# PD.net
KiCad netlist of a schematic drawn in Altium Designer
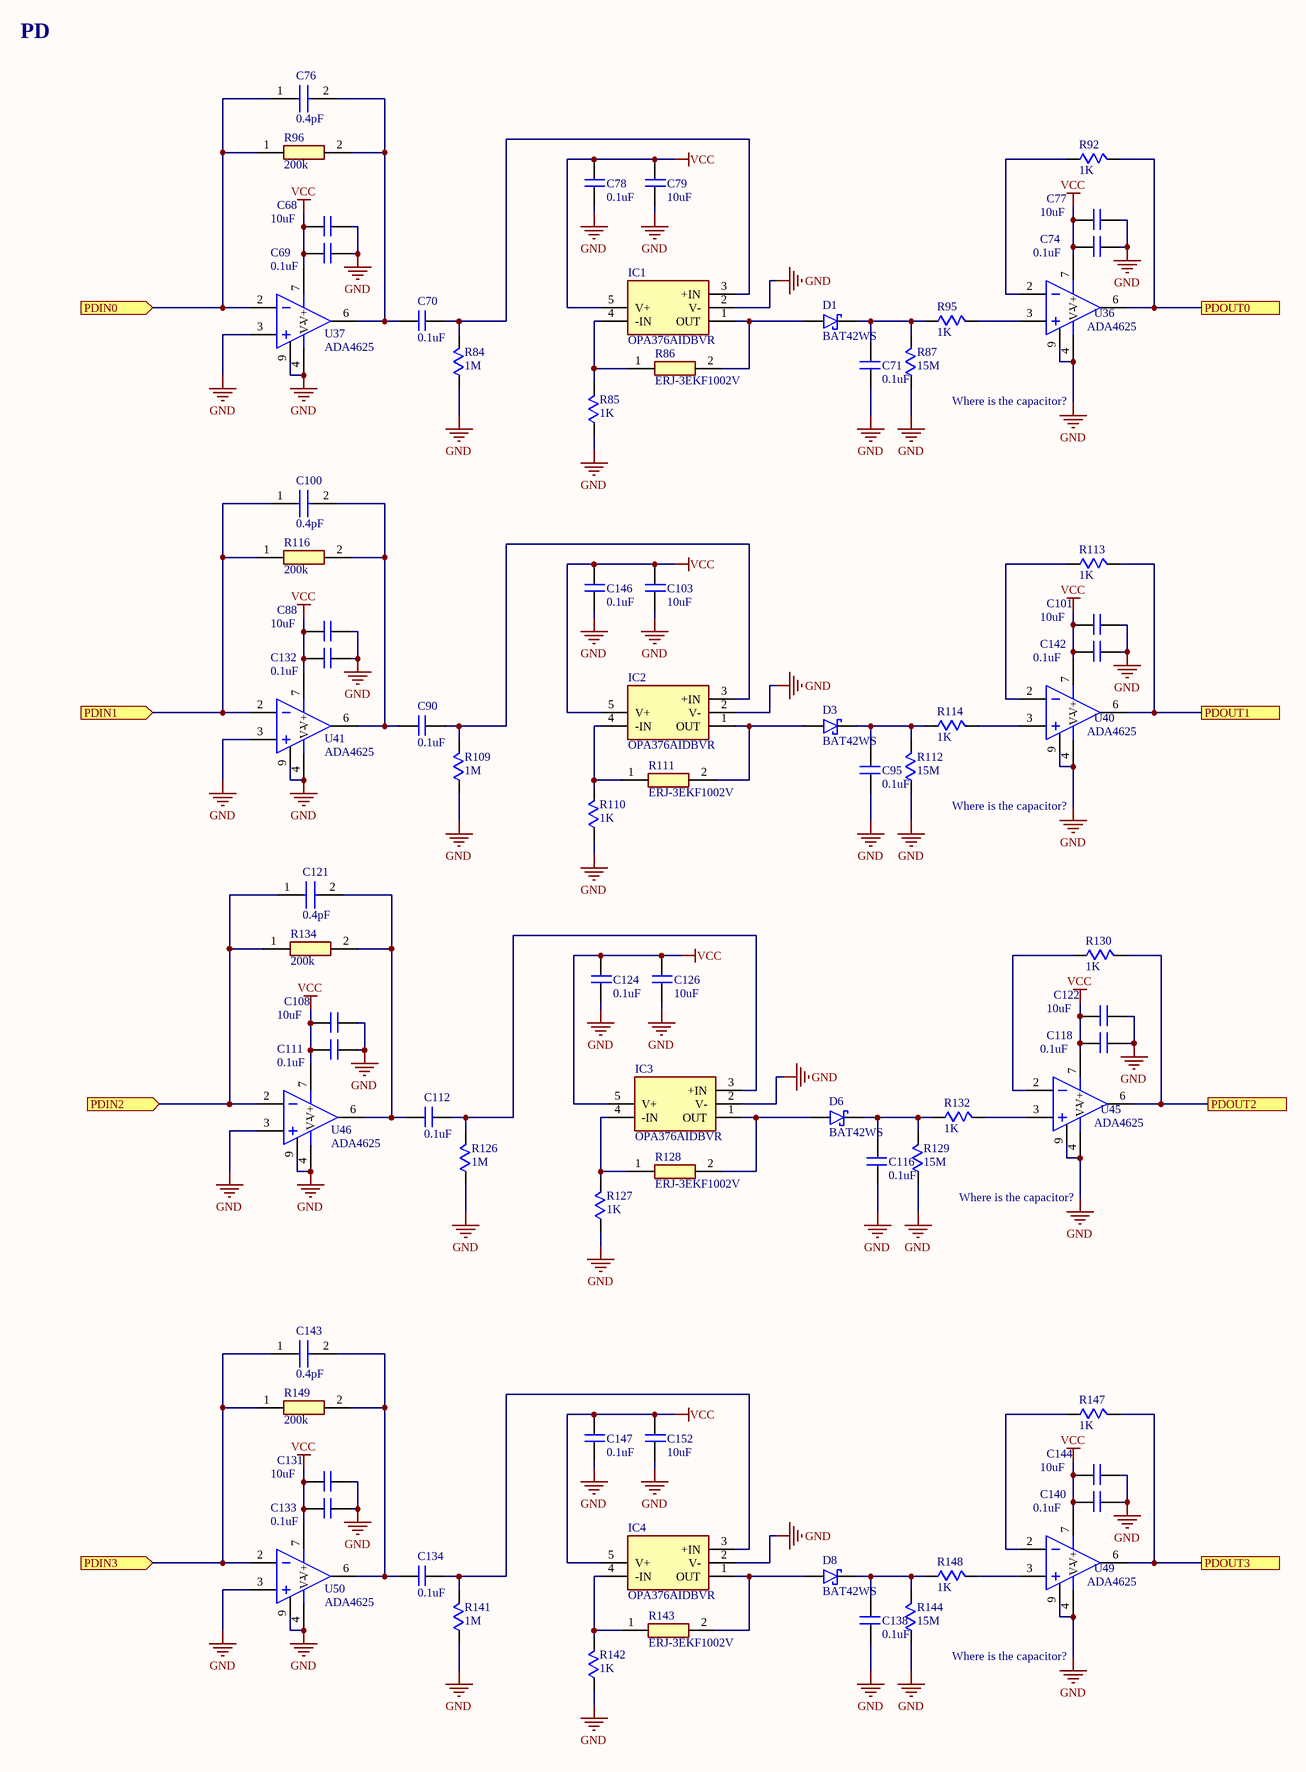
[diagram p0: PD.SchDoc]

(export (version "E")
  (design (tool "Eeschema 10.0.6"))
  (components
    (comp (ref "C68")
      (value "10uF")
      (footprint "CAP0805")
      (description "25V 10uF X7R ±10% 0805 Multilayer Ceramic Capacitors MLCC - SMD/SMT ROHS")
      (fields
        (field (name "MANUFACTURER") "Murata")
        (field (name "MANUFACTURER PART NUMBER") "GRM21BZ71E106KE15L")
      )
      (libsource (lib "Pilot") (part "Capacitor 10uF GRM21BZ71E106KE15L"))
    )
    (comp (ref "C69")
      (value "0.1uF")
      (footprint "CAP0603")
      (description "50V 100nF X5R 卤10% 0603 Multilayer Ceramic Capacitors MLCC - SMD/SMT ROHS")
      (fields
        (field (name "MANUFACTURER") "TDK")
        (field (name "MANUFACTURER PART NUMBER") "C1608X5R1H104K080AA")
      )
      (libsource (lib "Pilot") (part "Capacitor 0.1uF"))
    )
    (comp (ref "C70")
      (value "0.1uF")
      (footprint "CAP0603")
      (description "50V 100nF X5R 卤10% 0603 Multilayer Ceramic Capacitors MLCC - SMD/SMT ROHS")
      (fields
        (field (name "MANUFACTURER") "TDK")
        (field (name "MANUFACTURER PART NUMBER") "C1608X5R1H104K080AA")
      )
      (libsource (lib "Pilot") (part "Capacitor 0.1uF"))
    )
    (comp (ref "C71")
      (value "0.1uF")
      (footprint "CAP0603")
      (description "50V 100nF X5R 卤10% 0603 Multilayer Ceramic Capacitors MLCC - SMD/SMT ROHS")
      (fields
        (field (name "MANUFACTURER") "TDK")
        (field (name "MANUFACTURER PART NUMBER") "C1608X5R1H104K080AA")
      )
      (libsource (lib "Pilot") (part "Capacitor 0.1uF"))
    )
    (comp (ref "C74")
      (value "0.1uF")
      (footprint "CAP0603")
      (description "50V 100nF X5R 卤10% 0603 Multilayer Ceramic Capacitors MLCC - SMD/SMT ROHS")
      (fields
        (field (name "MANUFACTURER") "TDK")
        (field (name "MANUFACTURER PART NUMBER") "C1608X5R1H104K080AA")
      )
      (libsource (lib "Pilot") (part "Capacitor 0.1uF"))
    )
    (comp (ref "C76")
      (value "0.4pF")
      (footprint "CAPC1608X87N")
      (description "Capacitor")
      (fields (field (name "MANUFACTURER_PART_NUMBER") "CBR06C408B5GAC"))
      (libsource (lib "Pilot") (part "CBR06C408B5GAC"))
    )
    (comp (ref "C77")
      (value "10uF")
      (footprint "CAP0805")
      (description "25V 10uF X7R ±10% 0805 Multilayer Ceramic Capacitors MLCC - SMD/SMT ROHS")
      (fields
        (field (name "MANUFACTURER") "Murata")
        (field (name "MANUFACTURER PART NUMBER") "GRM21BZ71E106KE15L")
      )
      (libsource (lib "Pilot") (part "Capacitor 10uF GRM21BZ71E106KE15L"))
    )
    (comp (ref "C78")
      (value "0.1uF")
      (footprint "CAP0603")
      (description "50V 100nF X5R 卤10% 0603 Multilayer Ceramic Capacitors MLCC - SMD/SMT ROHS")
      (fields
        (field (name "MANUFACTURER") "TDK")
        (field (name "MANUFACTURER PART NUMBER") "C1608X5R1H104K080AA")
      )
      (libsource (lib "Pilot") (part "Capacitor 0.1uF"))
    )
    (comp (ref "C79")
      (value "10uF")
      (footprint "CAP0805")
      (description "25V 10uF X7R ±10% 0805 Multilayer Ceramic Capacitors MLCC - SMD/SMT ROHS")
      (fields
        (field (name "MANUFACTURER") "Murata")
        (field (name "MANUFACTURER PART NUMBER") "GRM21BZ71E106KE15L")
      )
      (libsource (lib "Pilot") (part "Capacitor 10uF GRM21BZ71E106KE15L"))
    )
    (comp (ref "C88")
      (value "10uF")
      (footprint "CAP0805")
      (description "25V 10uF X7R ±10% 0805 Multilayer Ceramic Capacitors MLCC - SMD/SMT ROHS")
      (fields
        (field (name "MANUFACTURER") "Murata")
        (field (name "MANUFACTURER PART NUMBER") "GRM21BZ71E106KE15L")
      )
      (libsource (lib "Pilot") (part "Capacitor 10uF GRM21BZ71E106KE15L"))
    )
    (comp (ref "C90")
      (value "0.1uF")
      (footprint "CAP0603")
      (description "50V 100nF X5R 卤10% 0603 Multilayer Ceramic Capacitors MLCC - SMD/SMT ROHS")
      (fields
        (field (name "MANUFACTURER") "TDK")
        (field (name "MANUFACTURER PART NUMBER") "C1608X5R1H104K080AA")
      )
      (libsource (lib "Pilot") (part "Capacitor 0.1uF"))
    )
    (comp (ref "C95")
      (value "0.1uF")
      (footprint "CAP0603")
      (description "50V 100nF X5R 卤10% 0603 Multilayer Ceramic Capacitors MLCC - SMD/SMT ROHS")
      (fields
        (field (name "MANUFACTURER") "TDK")
        (field (name "MANUFACTURER PART NUMBER") "C1608X5R1H104K080AA")
      )
      (libsource (lib "Pilot") (part "Capacitor 0.1uF"))
    )
    (comp (ref "C100")
      (value "0.4pF")
      (footprint "CAPC1608X87N")
      (description "Capacitor")
      (fields (field (name "MANUFACTURER_PART_NUMBER") "CBR06C408B5GAC"))
      (libsource (lib "Pilot") (part "CBR06C408B5GAC"))
    )
    (comp (ref "C101")
      (value "10uF")
      (footprint "CAP0805")
      (description "25V 10uF X7R ±10% 0805 Multilayer Ceramic Capacitors MLCC - SMD/SMT ROHS")
      (fields
        (field (name "MANUFACTURER") "Murata")
        (field (name "MANUFACTURER PART NUMBER") "GRM21BZ71E106KE15L")
      )
      (libsource (lib "Pilot") (part "Capacitor 10uF GRM21BZ71E106KE15L"))
    )
    (comp (ref "C103")
      (value "10uF")
      (footprint "CAP0805")
      (description "25V 10uF X7R ±10% 0805 Multilayer Ceramic Capacitors MLCC - SMD/SMT ROHS")
      (fields
        (field (name "MANUFACTURER") "Murata")
        (field (name "MANUFACTURER PART NUMBER") "GRM21BZ71E106KE15L")
      )
      (libsource (lib "Pilot") (part "Capacitor 10uF GRM21BZ71E106KE15L"))
    )
    (comp (ref "C108")
      (value "10uF")
      (footprint "CAP0805")
      (description "25V 10uF X7R ±10% 0805 Multilayer Ceramic Capacitors MLCC - SMD/SMT ROHS")
      (fields
        (field (name "MANUFACTURER") "Murata")
        (field (name "MANUFACTURER PART NUMBER") "GRM21BZ71E106KE15L")
      )
      (libsource (lib "Pilot") (part "Capacitor 10uF GRM21BZ71E106KE15L"))
    )
    (comp (ref "C111")
      (value "0.1uF")
      (footprint "CAP0603")
      (description "50V 100nF X5R 卤10% 0603 Multilayer Ceramic Capacitors MLCC - SMD/SMT ROHS")
      (fields
        (field (name "MANUFACTURER") "TDK")
        (field (name "MANUFACTURER PART NUMBER") "C1608X5R1H104K080AA")
      )
      (libsource (lib "Pilot") (part "Capacitor 0.1uF"))
    )
    (comp (ref "C112")
      (value "0.1uF")
      (footprint "CAP0603")
      (description "50V 100nF X5R 卤10% 0603 Multilayer Ceramic Capacitors MLCC - SMD/SMT ROHS")
      (fields
        (field (name "MANUFACTURER") "TDK")
        (field (name "MANUFACTURER PART NUMBER") "C1608X5R1H104K080AA")
      )
      (libsource (lib "Pilot") (part "Capacitor 0.1uF"))
    )
    (comp (ref "C116")
      (value "0.1uF")
      (footprint "CAP0603")
      (description "50V 100nF X5R 卤10% 0603 Multilayer Ceramic Capacitors MLCC - SMD/SMT ROHS")
      (fields
        (field (name "MANUFACTURER") "TDK")
        (field (name "MANUFACTURER PART NUMBER") "C1608X5R1H104K080AA")
      )
      (libsource (lib "Pilot") (part "Capacitor 0.1uF"))
    )
    (comp (ref "C118")
      (value "0.1uF")
      (footprint "CAP0603")
      (description "50V 100nF X5R 卤10% 0603 Multilayer Ceramic Capacitors MLCC - SMD/SMT ROHS")
      (fields
        (field (name "MANUFACTURER") "TDK")
        (field (name "MANUFACTURER PART NUMBER") "C1608X5R1H104K080AA")
      )
      (libsource (lib "Pilot") (part "Capacitor 0.1uF"))
    )
    (comp (ref "C121")
      (value "0.4pF")
      (footprint "CAPC1608X87N")
      (description "Capacitor")
      (fields (field (name "MANUFACTURER_PART_NUMBER") "CBR06C408B5GAC"))
      (libsource (lib "Pilot") (part "CBR06C408B5GAC"))
    )
    (comp (ref "C122")
      (value "10uF")
      (footprint "CAP0805")
      (description "25V 10uF X7R ±10% 0805 Multilayer Ceramic Capacitors MLCC - SMD/SMT ROHS")
      (fields
        (field (name "MANUFACTURER") "Murata")
        (field (name "MANUFACTURER PART NUMBER") "GRM21BZ71E106KE15L")
      )
      (libsource (lib "Pilot") (part "Capacitor 10uF GRM21BZ71E106KE15L"))
    )
    (comp (ref "C124")
      (value "0.1uF")
      (footprint "CAP0603")
      (description "50V 100nF X5R 卤10% 0603 Multilayer Ceramic Capacitors MLCC - SMD/SMT ROHS")
      (fields
        (field (name "MANUFACTURER") "TDK")
        (field (name "MANUFACTURER PART NUMBER") "C1608X5R1H104K080AA")
      )
      (libsource (lib "Pilot") (part "Capacitor 0.1uF"))
    )
    (comp (ref "C126")
      (value "10uF")
      (footprint "CAP0805")
      (description "25V 10uF X7R ±10% 0805 Multilayer Ceramic Capacitors MLCC - SMD/SMT ROHS")
      (fields
        (field (name "MANUFACTURER") "Murata")
        (field (name "MANUFACTURER PART NUMBER") "GRM21BZ71E106KE15L")
      )
      (libsource (lib "Pilot") (part "Capacitor 10uF GRM21BZ71E106KE15L"))
    )
    (comp (ref "C131")
      (value "10uF")
      (footprint "CAP0805")
      (description "25V 10uF X7R ±10% 0805 Multilayer Ceramic Capacitors MLCC - SMD/SMT ROHS")
      (fields
        (field (name "MANUFACTURER") "Murata")
        (field (name "MANUFACTURER PART NUMBER") "GRM21BZ71E106KE15L")
      )
      (libsource (lib "Pilot") (part "Capacitor 10uF GRM21BZ71E106KE15L"))
    )
    (comp (ref "C132")
      (value "0.1uF")
      (footprint "CAP0603")
      (description "50V 100nF X5R 卤10% 0603 Multilayer Ceramic Capacitors MLCC - SMD/SMT ROHS")
      (fields
        (field (name "MANUFACTURER") "TDK")
        (field (name "MANUFACTURER PART NUMBER") "C1608X5R1H104K080AA")
      )
      (libsource (lib "Pilot") (part "Capacitor 0.1uF"))
    )
    (comp (ref "C133")
      (value "0.1uF")
      (footprint "CAP0603")
      (description "50V 100nF X5R 卤10% 0603 Multilayer Ceramic Capacitors MLCC - SMD/SMT ROHS")
      (fields
        (field (name "MANUFACTURER") "TDK")
        (field (name "MANUFACTURER PART NUMBER") "C1608X5R1H104K080AA")
      )
      (libsource (lib "Pilot") (part "Capacitor 0.1uF"))
    )
    (comp (ref "C134")
      (value "0.1uF")
      (footprint "CAP0603")
      (description "50V 100nF X5R 卤10% 0603 Multilayer Ceramic Capacitors MLCC - SMD/SMT ROHS")
      (fields
        (field (name "MANUFACTURER") "TDK")
        (field (name "MANUFACTURER PART NUMBER") "C1608X5R1H104K080AA")
      )
      (libsource (lib "Pilot") (part "Capacitor 0.1uF"))
    )
    (comp (ref "C138")
      (value "0.1uF")
      (footprint "CAP0603")
      (description "50V 100nF X5R 卤10% 0603 Multilayer Ceramic Capacitors MLCC - SMD/SMT ROHS")
      (fields
        (field (name "MANUFACTURER") "TDK")
        (field (name "MANUFACTURER PART NUMBER") "C1608X5R1H104K080AA")
      )
      (libsource (lib "Pilot") (part "Capacitor 0.1uF"))
    )
    (comp (ref "C140")
      (value "0.1uF")
      (footprint "CAP0603")
      (description "50V 100nF X5R 卤10% 0603 Multilayer Ceramic Capacitors MLCC - SMD/SMT ROHS")
      (fields
        (field (name "MANUFACTURER") "TDK")
        (field (name "MANUFACTURER PART NUMBER") "C1608X5R1H104K080AA")
      )
      (libsource (lib "Pilot") (part "Capacitor 0.1uF"))
    )
    (comp (ref "C142")
      (value "0.1uF")
      (footprint "CAP0603")
      (description "50V 100nF X5R 卤10% 0603 Multilayer Ceramic Capacitors MLCC - SMD/SMT ROHS")
      (fields
        (field (name "MANUFACTURER") "TDK")
        (field (name "MANUFACTURER PART NUMBER") "C1608X5R1H104K080AA")
      )
      (libsource (lib "Pilot") (part "Capacitor 0.1uF"))
    )
    (comp (ref "C143")
      (value "0.4pF")
      (footprint "CAPC1608X87N")
      (description "Capacitor")
      (fields (field (name "MANUFACTURER_PART_NUMBER") "CBR06C408B5GAC"))
      (libsource (lib "Pilot") (part "CBR06C408B5GAC"))
    )
    (comp (ref "C144")
      (value "10uF")
      (footprint "CAP0805")
      (description "25V 10uF X7R ±10% 0805 Multilayer Ceramic Capacitors MLCC - SMD/SMT ROHS")
      (fields
        (field (name "MANUFACTURER") "Murata")
        (field (name "MANUFACTURER PART NUMBER") "GRM21BZ71E106KE15L")
      )
      (libsource (lib "Pilot") (part "Capacitor 10uF GRM21BZ71E106KE15L"))
    )
    (comp (ref "C146")
      (value "0.1uF")
      (footprint "CAP0603")
      (description "50V 100nF X5R 卤10% 0603 Multilayer Ceramic Capacitors MLCC - SMD/SMT ROHS")
      (fields
        (field (name "MANUFACTURER") "TDK")
        (field (name "MANUFACTURER PART NUMBER") "C1608X5R1H104K080AA")
      )
      (libsource (lib "Pilot") (part "Capacitor 0.1uF"))
    )
    (comp (ref "C147")
      (value "0.1uF")
      (footprint "CAP0603")
      (description "50V 100nF X5R 卤10% 0603 Multilayer Ceramic Capacitors MLCC - SMD/SMT ROHS")
      (fields
        (field (name "MANUFACTURER") "TDK")
        (field (name "MANUFACTURER PART NUMBER") "C1608X5R1H104K080AA")
      )
      (libsource (lib "Pilot") (part "Capacitor 0.1uF"))
    )
    (comp (ref "C152")
      (value "10uF")
      (footprint "CAP0805")
      (description "25V 10uF X7R ±10% 0805 Multilayer Ceramic Capacitors MLCC - SMD/SMT ROHS")
      (fields
        (field (name "MANUFACTURER") "Murata")
        (field (name "MANUFACTURER PART NUMBER") "GRM21BZ71E106KE15L")
      )
      (libsource (lib "Pilot") (part "Capacitor 10uF GRM21BZ71E106KE15L"))
    )
    (comp (ref "D1")
      (value "BAT42WS")
      (footprint "SOD-123")
      (description "Rectifier Diode, Schottky, 1 Phase, 1 Element, 0.2A, 30V V(RRM), Silicon")
      (fields
        (field (name "MANUFACTURER") "Vishay")
        (field (name "MANUFACTURER PART NUMBER") "BAT42WS-E3-18")
      )
      (libsource (lib "Pilot") (part "BAT42WS-E3-18"))
    )
    (comp (ref "D3")
      (value "BAT42WS")
      (footprint "SOD-123")
      (description "Rectifier Diode, Schottky, 1 Phase, 1 Element, 0.2A, 30V V(RRM), Silicon")
      (fields
        (field (name "MANUFACTURER") "Vishay")
        (field (name "MANUFACTURER PART NUMBER") "BAT42WS-E3-18")
      )
      (libsource (lib "Pilot") (part "BAT42WS-E3-18"))
    )
    (comp (ref "D6")
      (value "BAT42WS")
      (footprint "SOD-123")
      (description "Rectifier Diode, Schottky, 1 Phase, 1 Element, 0.2A, 30V V(RRM), Silicon")
      (fields
        (field (name "MANUFACTURER") "Vishay")
        (field (name "MANUFACTURER PART NUMBER") "BAT42WS-E3-18")
      )
      (libsource (lib "Pilot") (part "BAT42WS-E3-18"))
    )
    (comp (ref "D8")
      (value "BAT42WS")
      (footprint "SOD-123")
      (description "Rectifier Diode, Schottky, 1 Phase, 1 Element, 0.2A, 30V V(RRM), Silicon")
      (fields
        (field (name "MANUFACTURER") "Vishay")
        (field (name "MANUFACTURER PART NUMBER") "BAT42WS-E3-18")
      )
      (libsource (lib "Pilot") (part "BAT42WS-E3-18"))
    )
    (comp (ref "IC1")
      (value "OPA376AIDBVR")
      (footprint "SOT95P280X145-5N")
      (description "Integrated Circuit")
      (fields (field (name "MOUSER PART NUMBER") "595-OPA376AIDBVR"))
      (libsource (lib "Pilot") (part "OPA376AIDBVR"))
    )
    (comp (ref "IC2")
      (value "OPA376AIDBVR")
      (footprint "SOT95P280X145-5N")
      (description "Integrated Circuit")
      (fields (field (name "MOUSER PART NUMBER") "595-OPA376AIDBVR"))
      (libsource (lib "Pilot") (part "OPA376AIDBVR"))
    )
    (comp (ref "IC3")
      (value "OPA376AIDBVR")
      (footprint "SOT95P280X145-5N")
      (description "Integrated Circuit")
      (fields (field (name "MOUSER PART NUMBER") "595-OPA376AIDBVR"))
      (libsource (lib "Pilot") (part "OPA376AIDBVR"))
    )
    (comp (ref "IC4")
      (value "OPA376AIDBVR")
      (footprint "SOT95P280X145-5N")
      (description "Integrated Circuit")
      (fields (field (name "MOUSER PART NUMBER") "595-OPA376AIDBVR"))
      (libsource (lib "Pilot") (part "OPA376AIDBVR"))
    )
    (comp (ref "R84") (value "1M") (footprint "RES0603") (libsource (lib "Pilot") (part "Resistor 1M")))
    (comp (ref "R85") (value "1K") (footprint "RES0805") (libsource (lib "Pilot") (part "Resistor 1K")))
    (comp (ref "R86")
      (value "ERJ-3EKF1002V")
      (footprint "Pilot:RESC1608X55N")
      (description "Resistor")
      (fields (field (name "MOUSER PART NUMBER") "667-ERJ-3EKF1002V"))
      (libsource (lib "Pilot") (part "ERJ-3EKF1002V"))
    )
    (comp (ref "R87") (value "15M") (footprint "RES0603") (libsource (lib "Pilot") (part "Resistor 15M")))
    (comp (ref "R92") (value "1K") (footprint "RES0805") (libsource (lib "Pilot") (part "Resistor 1K")))
    (comp (ref "R95") (value "1K") (footprint "RES0805") (libsource (lib "Pilot") (part "Resistor 1K")))
    (comp (ref "R96")
      (value "200k")
      (footprint "ERA3AEB101V")
      (description "Resistor")
      (fields
        (field (name "MANUFACTURER_PART_NUMBER") "ERA-3AED204V")
        (field (name "MOUSER PART NUMBER") "667-ERA-3AED204V")
      )
      (libsource (lib "Pilot") (part "ERA-3AED204V"))
    )
    (comp (ref "R109") (value "1M") (footprint "RES0603") (libsource (lib "Pilot") (part "Resistor 1M")))
    (comp (ref "R110") (value "1K") (footprint "RES0805") (libsource (lib "Pilot") (part "Resistor 1K")))
    (comp (ref "R111")
      (value "ERJ-3EKF1002V")
      (footprint "Pilot:RESC1608X55N")
      (description "Resistor")
      (fields (field (name "MOUSER PART NUMBER") "667-ERJ-3EKF1002V"))
      (libsource (lib "Pilot") (part "ERJ-3EKF1002V"))
    )
    (comp (ref "R112") (value "15M") (footprint "RES0603") (libsource (lib "Pilot") (part "Resistor 15M")))
    (comp (ref "R113") (value "1K") (footprint "RES0805") (libsource (lib "Pilot") (part "Resistor 1K")))
    (comp (ref "R114") (value "1K") (footprint "RES0805") (libsource (lib "Pilot") (part "Resistor 1K")))
    (comp (ref "R116")
      (value "200k")
      (footprint "ERA3AEB101V")
      (description "Resistor")
      (fields
        (field (name "MANUFACTURER_PART_NUMBER") "ERA-3AED204V")
        (field (name "MOUSER PART NUMBER") "667-ERA-3AED204V")
      )
      (libsource (lib "Pilot") (part "ERA-3AED204V"))
    )
    (comp (ref "R126") (value "1M") (footprint "RES0603") (libsource (lib "Pilot") (part "Resistor 1M")))
    (comp (ref "R127") (value "1K") (footprint "RES0805") (libsource (lib "Pilot") (part "Resistor 1K")))
    (comp (ref "R128")
      (value "ERJ-3EKF1002V")
      (footprint "Pilot:RESC1608X55N")
      (description "Resistor")
      (fields (field (name "MOUSER PART NUMBER") "667-ERJ-3EKF1002V"))
      (libsource (lib "Pilot") (part "ERJ-3EKF1002V"))
    )
    (comp (ref "R129") (value "15M") (footprint "RES0603") (libsource (lib "Pilot") (part "Resistor 15M")))
    (comp (ref "R130") (value "1K") (footprint "RES0805") (libsource (lib "Pilot") (part "Resistor 1K")))
    (comp (ref "R132") (value "1K") (footprint "RES0805") (libsource (lib "Pilot") (part "Resistor 1K")))
    (comp (ref "R134")
      (value "200k")
      (footprint "ERA3AEB101V")
      (description "Resistor")
      (fields
        (field (name "MANUFACTURER_PART_NUMBER") "ERA-3AED204V")
        (field (name "MOUSER PART NUMBER") "667-ERA-3AED204V")
      )
      (libsource (lib "Pilot") (part "ERA-3AED204V"))
    )
    (comp (ref "R141") (value "1M") (footprint "RES0603") (libsource (lib "Pilot") (part "Resistor 1M")))
    (comp (ref "R142") (value "1K") (footprint "RES0805") (libsource (lib "Pilot") (part "Resistor 1K")))
    (comp (ref "R143")
      (value "ERJ-3EKF1002V")
      (footprint "Pilot:RESC1608X55N")
      (description "Resistor")
      (fields (field (name "MOUSER PART NUMBER") "667-ERJ-3EKF1002V"))
      (libsource (lib "Pilot") (part "ERJ-3EKF1002V"))
    )
    (comp (ref "R144") (value "15M") (footprint "RES0603") (libsource (lib "Pilot") (part "Resistor 15M")))
    (comp (ref "R147") (value "1K") (footprint "RES0805") (libsource (lib "Pilot") (part "Resistor 1K")))
    (comp (ref "R148") (value "1K") (footprint "RES0805") (libsource (lib "Pilot") (part "Resistor 1K")))
    (comp (ref "R149")
      (value "200k")
      (footprint "ERA3AEB101V")
      (description "Resistor")
      (fields
        (field (name "MANUFACTURER_PART_NUMBER") "ERA-3AED204V")
        (field (name "MOUSER PART NUMBER") "667-ERA-3AED204V")
      )
      (libsource (lib "Pilot") (part "ERA-3AED204V"))
    )
    (comp (ref "U36")
      (value "ADA4625")
      (footprint "SOIC8")
      (description "Op Amp Single Low Noise Amplifier R-R O/P ±18V/36V 8-Pin SOIC N EP Tube")
      (fields
        (field (name "MANUFACTURER") "Analog Devices")
        (field (name "MANUFACTURER PART NUMBER") "ADA4625-1ARDZ")
      )
      (libsource (lib "Pilot") (part "ADA4625-1ARDZ"))
    )
    (comp (ref "U37")
      (value "ADA4625")
      (footprint "SOIC8")
      (description "Op Amp Single Low Noise Amplifier R-R O/P ±18V/36V 8-Pin SOIC N EP Tube")
      (fields
        (field (name "MANUFACTURER") "Analog Devices")
        (field (name "MANUFACTURER PART NUMBER") "ADA4625-1ARDZ")
      )
      (libsource (lib "Pilot") (part "ADA4625-1ARDZ"))
    )
    (comp (ref "U40")
      (value "ADA4625")
      (footprint "SOIC8")
      (description "Op Amp Single Low Noise Amplifier R-R O/P ±18V/36V 8-Pin SOIC N EP Tube")
      (fields
        (field (name "MANUFACTURER") "Analog Devices")
        (field (name "MANUFACTURER PART NUMBER") "ADA4625-1ARDZ")
      )
      (libsource (lib "Pilot") (part "ADA4625-1ARDZ"))
    )
    (comp (ref "U41")
      (value "ADA4625")
      (footprint "SOIC8")
      (description "Op Amp Single Low Noise Amplifier R-R O/P ±18V/36V 8-Pin SOIC N EP Tube")
      (fields
        (field (name "MANUFACTURER") "Analog Devices")
        (field (name "MANUFACTURER PART NUMBER") "ADA4625-1ARDZ")
      )
      (libsource (lib "Pilot") (part "ADA4625-1ARDZ"))
    )
    (comp (ref "U45")
      (value "ADA4625")
      (footprint "SOIC8")
      (description "Op Amp Single Low Noise Amplifier R-R O/P ±18V/36V 8-Pin SOIC N EP Tube")
      (fields
        (field (name "MANUFACTURER") "Analog Devices")
        (field (name "MANUFACTURER PART NUMBER") "ADA4625-1ARDZ")
      )
      (libsource (lib "Pilot") (part "ADA4625-1ARDZ"))
    )
    (comp (ref "U46")
      (value "ADA4625")
      (footprint "SOIC8")
      (description "Op Amp Single Low Noise Amplifier R-R O/P ±18V/36V 8-Pin SOIC N EP Tube")
      (fields
        (field (name "MANUFACTURER") "Analog Devices")
        (field (name "MANUFACTURER PART NUMBER") "ADA4625-1ARDZ")
      )
      (libsource (lib "Pilot") (part "ADA4625-1ARDZ"))
    )
    (comp (ref "U49")
      (value "ADA4625")
      (footprint "SOIC8")
      (description "Op Amp Single Low Noise Amplifier R-R O/P ±18V/36V 8-Pin SOIC N EP Tube")
      (fields
        (field (name "MANUFACTURER") "Analog Devices")
        (field (name "MANUFACTURER PART NUMBER") "ADA4625-1ARDZ")
      )
      (libsource (lib "Pilot") (part "ADA4625-1ARDZ"))
    )
    (comp (ref "U50")
      (value "ADA4625")
      (footprint "SOIC8")
      (description "Op Amp Single Low Noise Amplifier R-R O/P ±18V/36V 8-Pin SOIC N EP Tube")
      (fields
        (field (name "MANUFACTURER") "Analog Devices")
        (field (name "MANUFACTURER PART NUMBER") "ADA4625-1ARDZ")
      )
      (libsource (lib "Pilot") (part "ADA4625-1ARDZ"))
    )
  )
  (nets
    (net (code "1") (name "/PDIN0") (class "Default")
      (node (ref "C76") (pin "1") (pinfunction "1_1") (pintype "passive"))
      (node (ref "R96") (pin "1") (pinfunction "1_1") (pintype "passive"))
      (node (ref "U37") (pin "2") (pinfunction "IN-_2") (pintype "passive"))
    )
    (net (code "2") (name "/PDIN1") (class "Default")
      (node (ref "C100") (pin "1") (pinfunction "1_1") (pintype "passive"))
      (node (ref "R116") (pin "1") (pinfunction "1_1") (pintype "passive"))
      (node (ref "U41") (pin "2") (pinfunction "IN-_2") (pintype "passive"))
    )
    (net (code "3") (name "/PDIN2") (class "Default")
      (node (ref "C121") (pin "1") (pinfunction "1_1") (pintype "passive"))
      (node (ref "R134") (pin "1") (pinfunction "1_1") (pintype "passive"))
      (node (ref "U46") (pin "2") (pinfunction "IN-_2") (pintype "passive"))
    )
    (net (code "4") (name "/PDIN3") (class "Default")
      (node (ref "C143") (pin "1") (pinfunction "1_1") (pintype "passive"))
      (node (ref "R149") (pin "1") (pinfunction "1_1") (pintype "passive"))
      (node (ref "U50") (pin "2") (pinfunction "IN-_2") (pintype "passive"))
    )
    (net (code "5") (name "/PDOUT0") (class "Default")
      (node (ref "R92") (pin "2") (pinfunction "2_2") (pintype "passive"))
      (node (ref "U36") (pin "6") (pinfunction "OUT_6") (pintype "passive"))
    )
    (net (code "6") (name "/PDOUT1") (class "Default")
      (node (ref "R113") (pin "2") (pinfunction "2_2") (pintype "passive"))
      (node (ref "U40") (pin "6") (pinfunction "OUT_6") (pintype "passive"))
    )
    (net (code "7") (name "/PDOUT2") (class "Default")
      (node (ref "R130") (pin "2") (pinfunction "2_2") (pintype "passive"))
      (node (ref "U45") (pin "6") (pinfunction "OUT_6") (pintype "passive"))
    )
    (net (code "8") (name "/PDOUT3") (class "Default")
      (node (ref "R147") (pin "2") (pinfunction "2_2") (pintype "passive"))
      (node (ref "U49") (pin "6") (pinfunction "OUT_6") (pintype "passive"))
    )
    (net (code "9") (name "GND") (class "Default")
      (node (ref "C101") (pin "2") (pinfunction "2_2") (pintype "passive"))
      (node (ref "C103") (pin "2") (pinfunction "2_2") (pintype "passive"))
      (node (ref "C108") (pin "2") (pinfunction "2_2") (pintype "passive"))
      (node (ref "C111") (pin "2") (pinfunction "2_2") (pintype "passive"))
      (node (ref "C116") (pin "1") (pinfunction "1_1") (pintype "passive"))
      (node (ref "C118") (pin "2") (pinfunction "2_2") (pintype "passive"))
      (node (ref "C122") (pin "2") (pinfunction "2_2") (pintype "passive"))
      (node (ref "C124") (pin "2") (pinfunction "2_2") (pintype "passive"))
      (node (ref "C126") (pin "2") (pinfunction "2_2") (pintype "passive"))
      (node (ref "C131") (pin "2") (pinfunction "2_2") (pintype "passive"))
      (node (ref "C132") (pin "2") (pinfunction "2_2") (pintype "passive"))
      (node (ref "C133") (pin "2") (pinfunction "2_2") (pintype "passive"))
      (node (ref "C138") (pin "1") (pinfunction "1_1") (pintype "passive"))
      (node (ref "C140") (pin "2") (pinfunction "2_2") (pintype "passive"))
      (node (ref "C142") (pin "2") (pinfunction "2_2") (pintype "passive"))
      (node (ref "C144") (pin "2") (pinfunction "2_2") (pintype "passive"))
      (node (ref "C146") (pin "2") (pinfunction "2_2") (pintype "passive"))
      (node (ref "C147") (pin "2") (pinfunction "2_2") (pintype "passive"))
      (node (ref "C152") (pin "2") (pinfunction "2_2") (pintype "passive"))
      (node (ref "C68") (pin "2") (pinfunction "2_2") (pintype "passive"))
      (node (ref "C69") (pin "2") (pinfunction "2_2") (pintype "passive"))
      (node (ref "C71") (pin "1") (pinfunction "1_1") (pintype "passive"))
      (node (ref "C74") (pin "2") (pinfunction "2_2") (pintype "passive"))
      (node (ref "C77") (pin "2") (pinfunction "2_2") (pintype "passive"))
      (node (ref "C78") (pin "2") (pinfunction "2_2") (pintype "passive"))
      (node (ref "C79") (pin "2") (pinfunction "2_2") (pintype "passive"))
      (node (ref "C88") (pin "2") (pinfunction "2_2") (pintype "passive"))
      (node (ref "C95") (pin "1") (pinfunction "1_1") (pintype "passive"))
      (node (ref "IC1") (pin "2") (pinfunction "V-_2") (pintype "passive"))
      (node (ref "IC2") (pin "2") (pinfunction "V-_2") (pintype "passive"))
      (node (ref "IC3") (pin "2") (pinfunction "V-_2") (pintype "passive"))
      (node (ref "IC4") (pin "2") (pinfunction "V-_2") (pintype "passive"))
      (node (ref "R109") (pin "1") (pinfunction "1_1") (pintype "passive"))
      (node (ref "R110") (pin "1") (pinfunction "1_1") (pintype "passive"))
      (node (ref "R112") (pin "1") (pinfunction "1_1") (pintype "passive"))
      (node (ref "R126") (pin "1") (pinfunction "1_1") (pintype "passive"))
      (node (ref "R127") (pin "1") (pinfunction "1_1") (pintype "passive"))
      (node (ref "R129") (pin "1") (pinfunction "1_1") (pintype "passive"))
      (node (ref "R141") (pin "1") (pinfunction "1_1") (pintype "passive"))
      (node (ref "R142") (pin "1") (pinfunction "1_1") (pintype "passive"))
      (node (ref "R144") (pin "1") (pinfunction "1_1") (pintype "passive"))
      (node (ref "R84") (pin "1") (pinfunction "1_1") (pintype "passive"))
      (node (ref "R85") (pin "1") (pinfunction "1_1") (pintype "passive"))
      (node (ref "R87") (pin "1") (pinfunction "1_1") (pintype "passive"))
      (node (ref "U36") (pin "4") (pinfunction "V-_4") (pintype "power_in"))
      (node (ref "U36") (pin "9") (pinfunction "9_9") (pintype "passive"))
      (node (ref "U37") (pin "3") (pinfunction "IN+_3") (pintype "passive"))
      (node (ref "U37") (pin "4") (pinfunction "V-_4") (pintype "power_in"))
      (node (ref "U37") (pin "9") (pinfunction "9_9") (pintype "passive"))
      (node (ref "U40") (pin "4") (pinfunction "V-_4") (pintype "power_in"))
      (node (ref "U40") (pin "9") (pinfunction "9_9") (pintype "passive"))
      (node (ref "U41") (pin "3") (pinfunction "IN+_3") (pintype "passive"))
      (node (ref "U41") (pin "4") (pinfunction "V-_4") (pintype "power_in"))
      (node (ref "U41") (pin "9") (pinfunction "9_9") (pintype "passive"))
      (node (ref "U45") (pin "4") (pinfunction "V-_4") (pintype "power_in"))
      (node (ref "U45") (pin "9") (pinfunction "9_9") (pintype "passive"))
      (node (ref "U46") (pin "3") (pinfunction "IN+_3") (pintype "passive"))
      (node (ref "U46") (pin "4") (pinfunction "V-_4") (pintype "power_in"))
      (node (ref "U46") (pin "9") (pinfunction "9_9") (pintype "passive"))
      (node (ref "U49") (pin "4") (pinfunction "V-_4") (pintype "power_in"))
      (node (ref "U49") (pin "9") (pinfunction "9_9") (pintype "passive"))
      (node (ref "U50") (pin "3") (pinfunction "IN+_3") (pintype "passive"))
      (node (ref "U50") (pin "4") (pinfunction "V-_4") (pintype "power_in"))
      (node (ref "U50") (pin "9") (pinfunction "9_9") (pintype "passive"))
    )
    (net (code "10") (name "Net-(C71-Pad2)") (class "Default")
      (node (ref "C71") (pin "2") (pinfunction "2_2") (pintype "passive"))
      (node (ref "D1") (pin "1") (pinfunction "1_1") (pintype "passive"))
      (node (ref "R87") (pin "2") (pinfunction "2_2") (pintype "passive"))
      (node (ref "R95") (pin "1") (pinfunction "1_1") (pintype "passive"))
    )
    (net (code "11") (name "Net-(C95-Pad2)") (class "Default")
      (node (ref "C95") (pin "2") (pinfunction "2_2") (pintype "passive"))
      (node (ref "D3") (pin "1") (pinfunction "1_1") (pintype "passive"))
      (node (ref "R112") (pin "2") (pinfunction "2_2") (pintype "passive"))
      (node (ref "R114") (pin "1") (pinfunction "1_1") (pintype "passive"))
    )
    (net (code "12") (name "Net-(C116-Pad2)") (class "Default")
      (node (ref "C116") (pin "2") (pinfunction "2_2") (pintype "passive"))
      (node (ref "D6") (pin "1") (pinfunction "1_1") (pintype "passive"))
      (node (ref "R129") (pin "2") (pinfunction "2_2") (pintype "passive"))
      (node (ref "R132") (pin "1") (pinfunction "1_1") (pintype "passive"))
    )
    (net (code "13") (name "Net-(C138-Pad2)") (class "Default")
      (node (ref "C138") (pin "2") (pinfunction "2_2") (pintype "passive"))
      (node (ref "D8") (pin "1") (pinfunction "1_1") (pintype "passive"))
      (node (ref "R144") (pin "2") (pinfunction "2_2") (pintype "passive"))
      (node (ref "R148") (pin "1") (pinfunction "1_1") (pintype "passive"))
    )
    (net (code "14") (name "Net-(IC1-+IN)") (class "Default")
      (node (ref "C70") (pin "2") (pinfunction "2_2") (pintype "passive"))
      (node (ref "IC1") (pin "3") (pinfunction "+IN_3") (pintype "passive"))
      (node (ref "R84") (pin "2") (pinfunction "2_2") (pintype "passive"))
    )
    (net (code "15") (name "Net-(IC1--IN)") (class "Default")
      (node (ref "IC1") (pin "4") (pinfunction "-IN_4") (pintype "passive"))
      (node (ref "R85") (pin "2") (pinfunction "2_2") (pintype "passive"))
      (node (ref "R86") (pin "1") (pinfunction "1_1") (pintype "passive"))
    )
    (net (code "16") (name "Net-(IC1-OUT)") (class "Default")
      (node (ref "D1") (pin "2") (pinfunction "2_2") (pintype "passive"))
      (node (ref "IC1") (pin "1") (pinfunction "OUT_1") (pintype "passive"))
      (node (ref "R86") (pin "2") (pinfunction "2_2") (pintype "passive"))
    )
    (net (code "17") (name "Net-(IC2-+IN)") (class "Default")
      (node (ref "C90") (pin "2") (pinfunction "2_2") (pintype "passive"))
      (node (ref "IC2") (pin "3") (pinfunction "+IN_3") (pintype "passive"))
      (node (ref "R109") (pin "2") (pinfunction "2_2") (pintype "passive"))
    )
    (net (code "18") (name "Net-(IC2--IN)") (class "Default")
      (node (ref "IC2") (pin "4") (pinfunction "-IN_4") (pintype "passive"))
      (node (ref "R110") (pin "2") (pinfunction "2_2") (pintype "passive"))
      (node (ref "R111") (pin "1") (pinfunction "1_1") (pintype "passive"))
    )
    (net (code "19") (name "Net-(IC2-OUT)") (class "Default")
      (node (ref "D3") (pin "2") (pinfunction "2_2") (pintype "passive"))
      (node (ref "IC2") (pin "1") (pinfunction "OUT_1") (pintype "passive"))
      (node (ref "R111") (pin "2") (pinfunction "2_2") (pintype "passive"))
    )
    (net (code "20") (name "Net-(IC3-+IN)") (class "Default")
      (node (ref "C112") (pin "2") (pinfunction "2_2") (pintype "passive"))
      (node (ref "IC3") (pin "3") (pinfunction "+IN_3") (pintype "passive"))
      (node (ref "R126") (pin "2") (pinfunction "2_2") (pintype "passive"))
    )
    (net (code "21") (name "Net-(IC3--IN)") (class "Default")
      (node (ref "IC3") (pin "4") (pinfunction "-IN_4") (pintype "passive"))
      (node (ref "R127") (pin "2") (pinfunction "2_2") (pintype "passive"))
      (node (ref "R128") (pin "1") (pinfunction "1_1") (pintype "passive"))
    )
    (net (code "22") (name "Net-(IC3-OUT)") (class "Default")
      (node (ref "D6") (pin "2") (pinfunction "2_2") (pintype "passive"))
      (node (ref "IC3") (pin "1") (pinfunction "OUT_1") (pintype "passive"))
      (node (ref "R128") (pin "2") (pinfunction "2_2") (pintype "passive"))
    )
    (net (code "23") (name "Net-(IC4-+IN)") (class "Default")
      (node (ref "C134") (pin "2") (pinfunction "2_2") (pintype "passive"))
      (node (ref "IC4") (pin "3") (pinfunction "+IN_3") (pintype "passive"))
      (node (ref "R141") (pin "2") (pinfunction "2_2") (pintype "passive"))
    )
    (net (code "24") (name "Net-(IC4--IN)") (class "Default")
      (node (ref "IC4") (pin "4") (pinfunction "-IN_4") (pintype "passive"))
      (node (ref "R142") (pin "2") (pinfunction "2_2") (pintype "passive"))
      (node (ref "R143") (pin "1") (pinfunction "1_1") (pintype "passive"))
    )
    (net (code "25") (name "Net-(IC4-OUT)") (class "Default")
      (node (ref "D8") (pin "2") (pinfunction "2_2") (pintype "passive"))
      (node (ref "IC4") (pin "1") (pinfunction "OUT_1") (pintype "passive"))
      (node (ref "R143") (pin "2") (pinfunction "2_2") (pintype "passive"))
    )
    (net (code "26") (name "Net-(U36-IN+)") (class "Default")
      (node (ref "R95") (pin "2") (pinfunction "2_2") (pintype "passive"))
      (node (ref "U36") (pin "3") (pinfunction "IN+_3") (pintype "passive"))
    )
    (net (code "27") (name "Net-(U36-IN-)") (class "Default")
      (node (ref "R92") (pin "1") (pinfunction "1_1") (pintype "passive"))
      (node (ref "U36") (pin "2") (pinfunction "IN-_2") (pintype "passive"))
    )
    (net (code "28") (name "Net-(U37-OUT)") (class "Default")
      (node (ref "C70") (pin "1") (pinfunction "1_1") (pintype "passive"))
      (node (ref "C76") (pin "2") (pinfunction "2_2") (pintype "passive"))
      (node (ref "R96") (pin "2") (pinfunction "2_2") (pintype "passive"))
      (node (ref "U37") (pin "6") (pinfunction "OUT_6") (pintype "passive"))
    )
    (net (code "29") (name "Net-(U40-IN+)") (class "Default")
      (node (ref "R114") (pin "2") (pinfunction "2_2") (pintype "passive"))
      (node (ref "U40") (pin "3") (pinfunction "IN+_3") (pintype "passive"))
    )
    (net (code "30") (name "Net-(U40-IN-)") (class "Default")
      (node (ref "R113") (pin "1") (pinfunction "1_1") (pintype "passive"))
      (node (ref "U40") (pin "2") (pinfunction "IN-_2") (pintype "passive"))
    )
    (net (code "31") (name "Net-(U41-OUT)") (class "Default")
      (node (ref "C100") (pin "2") (pinfunction "2_2") (pintype "passive"))
      (node (ref "C90") (pin "1") (pinfunction "1_1") (pintype "passive"))
      (node (ref "R116") (pin "2") (pinfunction "2_2") (pintype "passive"))
      (node (ref "U41") (pin "6") (pinfunction "OUT_6") (pintype "passive"))
    )
    (net (code "32") (name "Net-(U45-IN+)") (class "Default")
      (node (ref "R132") (pin "2") (pinfunction "2_2") (pintype "passive"))
      (node (ref "U45") (pin "3") (pinfunction "IN+_3") (pintype "passive"))
    )
    (net (code "33") (name "Net-(U45-IN-)") (class "Default")
      (node (ref "R130") (pin "1") (pinfunction "1_1") (pintype "passive"))
      (node (ref "U45") (pin "2") (pinfunction "IN-_2") (pintype "passive"))
    )
    (net (code "34") (name "Net-(U46-OUT)") (class "Default")
      (node (ref "C112") (pin "1") (pinfunction "1_1") (pintype "passive"))
      (node (ref "C121") (pin "2") (pinfunction "2_2") (pintype "passive"))
      (node (ref "R134") (pin "2") (pinfunction "2_2") (pintype "passive"))
      (node (ref "U46") (pin "6") (pinfunction "OUT_6") (pintype "passive"))
    )
    (net (code "35") (name "Net-(U49-IN+)") (class "Default")
      (node (ref "R148") (pin "2") (pinfunction "2_2") (pintype "passive"))
      (node (ref "U49") (pin "3") (pinfunction "IN+_3") (pintype "passive"))
    )
    (net (code "36") (name "Net-(U49-IN-)") (class "Default")
      (node (ref "R147") (pin "1") (pinfunction "1_1") (pintype "passive"))
      (node (ref "U49") (pin "2") (pinfunction "IN-_2") (pintype "passive"))
    )
    (net (code "37") (name "Net-(U50-OUT)") (class "Default")
      (node (ref "C134") (pin "1") (pinfunction "1_1") (pintype "passive"))
      (node (ref "C143") (pin "2") (pinfunction "2_2") (pintype "passive"))
      (node (ref "R149") (pin "2") (pinfunction "2_2") (pintype "passive"))
      (node (ref "U50") (pin "6") (pinfunction "OUT_6") (pintype "passive"))
    )
    (net (code "38") (name "VCC") (class "Default")
      (node (ref "C101") (pin "1") (pinfunction "1_1") (pintype "passive"))
      (node (ref "C103") (pin "1") (pinfunction "1_1") (pintype "passive"))
      (node (ref "C108") (pin "1") (pinfunction "1_1") (pintype "passive"))
      (node (ref "C111") (pin "1") (pinfunction "1_1") (pintype "passive"))
      (node (ref "C118") (pin "1") (pinfunction "1_1") (pintype "passive"))
      (node (ref "C122") (pin "1") (pinfunction "1_1") (pintype "passive"))
      (node (ref "C124") (pin "1") (pinfunction "1_1") (pintype "passive"))
      (node (ref "C126") (pin "1") (pinfunction "1_1") (pintype "passive"))
      (node (ref "C131") (pin "1") (pinfunction "1_1") (pintype "passive"))
      (node (ref "C132") (pin "1") (pinfunction "1_1") (pintype "passive"))
      (node (ref "C133") (pin "1") (pinfunction "1_1") (pintype "passive"))
      (node (ref "C140") (pin "1") (pinfunction "1_1") (pintype "passive"))
      (node (ref "C142") (pin "1") (pinfunction "1_1") (pintype "passive"))
      (node (ref "C144") (pin "1") (pinfunction "1_1") (pintype "passive"))
      (node (ref "C146") (pin "1") (pinfunction "1_1") (pintype "passive"))
      (node (ref "C147") (pin "1") (pinfunction "1_1") (pintype "passive"))
      (node (ref "C152") (pin "1") (pinfunction "1_1") (pintype "passive"))
      (node (ref "C68") (pin "1") (pinfunction "1_1") (pintype "passive"))
      (node (ref "C69") (pin "1") (pinfunction "1_1") (pintype "passive"))
      (node (ref "C74") (pin "1") (pinfunction "1_1") (pintype "passive"))
      (node (ref "C77") (pin "1") (pinfunction "1_1") (pintype "passive"))
      (node (ref "C78") (pin "1") (pinfunction "1_1") (pintype "passive"))
      (node (ref "C79") (pin "1") (pinfunction "1_1") (pintype "passive"))
      (node (ref "C88") (pin "1") (pinfunction "1_1") (pintype "passive"))
      (node (ref "IC1") (pin "5") (pinfunction "V+_5") (pintype "passive"))
      (node (ref "IC2") (pin "5") (pinfunction "V+_5") (pintype "passive"))
      (node (ref "IC3") (pin "5") (pinfunction "V+_5") (pintype "passive"))
      (node (ref "IC4") (pin "5") (pinfunction "V+_5") (pintype "passive"))
      (node (ref "U36") (pin "7") (pinfunction "V+_7") (pintype "power_in"))
      (node (ref "U37") (pin "7") (pinfunction "V+_7") (pintype "power_in"))
      (node (ref "U40") (pin "7") (pinfunction "V+_7") (pintype "power_in"))
      (node (ref "U41") (pin "7") (pinfunction "V+_7") (pintype "power_in"))
      (node (ref "U45") (pin "7") (pinfunction "V+_7") (pintype "power_in"))
      (node (ref "U46") (pin "7") (pinfunction "V+_7") (pintype "power_in"))
      (node (ref "U49") (pin "7") (pinfunction "V+_7") (pintype "power_in"))
      (node (ref "U50") (pin "7") (pinfunction "V+_7") (pintype "power_in"))
    )
  )
)
